# PSIO_Switchboard_PU-20_v1.net
KiCad netlist of a schematic drawn in EAGLE
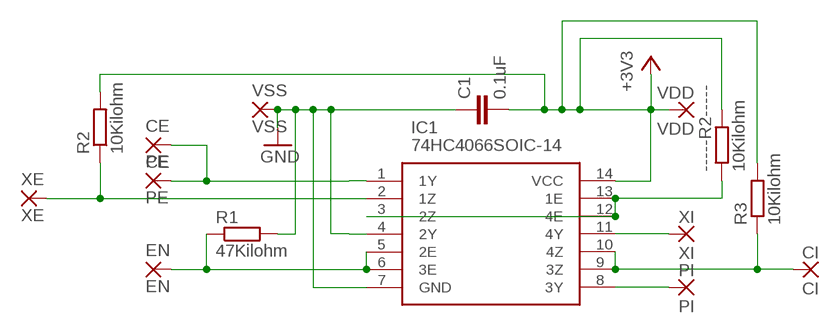
[diagram p0: schematic, sheet 1]

(export (version "E")
  (design (tool "Eeschema 10.0.6"))
  (components
    (comp (ref "-----R2-----")
      (value "10Kilohm")
      (footprint "eagle-import:R0805")
      (libsource (lib "eagle-import") (part "RESISTORSR0805"))
    )
    (comp (ref "C1")
      (value "0.1uF")
      (footprint "eagle-import:C0805")
      (libsource (lib "eagle-import") (part "CAPACITORSC0805"))
    )
    (comp (ref "CE")
      (value "CE")
      (footprint "eagle-import:CIRCLE-2X2")
      (libsource (lib "eagle-import") (part "PADSCIRCLE-2X2"))
    )
    (comp (ref "CI")
      (value "CI")
      (footprint "eagle-import:CIRCLE-2X2")
      (libsource (lib "eagle-import") (part "PADSCIRCLE-2X2"))
    )
    (comp (ref "EN")
      (value "EN")
      (footprint "eagle-import:CIRCLE-2X2")
      (libsource (lib "eagle-import") (part "PADSCIRCLE-2X2"))
    )
    (comp (ref "IC1")
      (value "74HC4066SOIC-14")
      (footprint "eagle-import:SOIC-14")
      (libsource (lib "eagle-import") (part "74HC4066SOIC-14"))
    )
    (comp (ref "PE")
      (value "PE")
      (footprint "eagle-import:CIRCLE-2X2")
      (libsource (lib "eagle-import") (part "PADSCIRCLE-2X2"))
    )
    (comp (ref "PI")
      (value "PI")
      (footprint "eagle-import:CIRCLE-2X2")
      (libsource (lib "eagle-import") (part "PADSCIRCLE-2X2"))
    )
    (comp (ref "R1")
      (value "47Kilohm")
      (footprint "eagle-import:R0805")
      (libsource (lib "eagle-import") (part "RESISTORSR0805"))
    )
    (comp (ref "R2")
      (value "10Kilohm")
      (footprint "eagle-import:R0805")
      (libsource (lib "eagle-import") (part "RESISTORSR0805"))
    )
    (comp (ref "R3")
      (value "10Kilohm")
      (footprint "eagle-import:R0805")
      (libsource (lib "eagle-import") (part "RESISTORSR0805"))
    )
    (comp (ref "VDD")
      (value "VDD")
      (footprint "eagle-import:CIRCLE-2X2")
      (libsource (lib "eagle-import") (part "PADSCIRCLE-2X2"))
    )
    (comp (ref "VSS")
      (value "VSS")
      (footprint "eagle-import:CIRCLE-2X2")
      (libsource (lib "eagle-import") (part "PADSCIRCLE-2X2"))
    )
    (comp (ref "XE")
      (value "XE")
      (footprint "eagle-import:CIRCLE-2X2")
      (libsource (lib "eagle-import") (part "PADSCIRCLE-2X2"))
    )
    (comp (ref "XI")
      (value "XI")
      (footprint "eagle-import:CIRCLE-2X2")
      (libsource (lib "eagle-import") (part "PADSCIRCLE-2X2"))
    )
  )
  (nets
    (net (code "1") (name "+3V3") (class "Default")
      (node (ref "-----R2-----") (pin "2") (pinfunction "2_2") (pintype "passive"))
      (node (ref "C1") (pin "2") (pinfunction "2_2") (pintype "passive"))
      (node (ref "IC1") (pin "14") (pinfunction "VCC_14") (pintype "bidirectional"))
      (node (ref "R2") (pin "2") (pinfunction "2_2") (pintype "passive"))
      (node (ref "R3") (pin "2") (pinfunction "2_2") (pintype "passive"))
      (node (ref "VDD") (pin "1") (pinfunction "P_1") (pintype "passive"))
    )
    (net (code "2") (name "GND") (class "Default")
      (node (ref "C1") (pin "1") (pinfunction "1_1") (pintype "passive"))
      (node (ref "IC1") (pin "4") (pinfunction "2Y_4") (pintype "bidirectional"))
      (node (ref "IC1") (pin "7") (pinfunction "GND_7") (pintype "bidirectional"))
      (node (ref "R1") (pin "2") (pinfunction "2_2") (pintype "passive"))
      (node (ref "VSS") (pin "1") (pinfunction "P_1") (pintype "passive"))
    )
    (net (code "3") (name "Net-(CE-P)") (class "Default")
      (node (ref "CE") (pin "1") (pinfunction "P_1") (pintype "passive"))
      (node (ref "IC1") (pin "1") (pinfunction "1Y_1") (pintype "bidirectional"))
      (node (ref "PE") (pin "1") (pinfunction "P_1") (pintype "passive"))
    )
    (net (code "4") (name "Net-(CI-P)") (class "Default")
      (node (ref "CI") (pin "1") (pinfunction "P_1") (pintype "passive"))
      (node (ref "IC1") (pin "10") (pinfunction "4Z_10") (pintype "bidirectional"))
      (node (ref "IC1") (pin "9") (pinfunction "3Z_9") (pintype "bidirectional"))
      (node (ref "R3") (pin "1") (pinfunction "1_1") (pintype "passive"))
    )
    (net (code "5") (name "Net-(EN-P)") (class "Default")
      (node (ref "EN") (pin "1") (pinfunction "P_1") (pintype "passive"))
      (node (ref "IC1") (pin "5") (pinfunction "2E_5") (pintype "bidirectional"))
      (node (ref "IC1") (pin "6") (pinfunction "3E_6") (pintype "bidirectional"))
      (node (ref "R1") (pin "1") (pinfunction "1_1") (pintype "passive"))
    )
    (net (code "6") (name "Net-(IC1-1E)") (class "Default")
      (node (ref "-----R2-----") (pin "1") (pinfunction "1_1") (pintype "passive"))
      (node (ref "IC1") (pin "12") (pinfunction "4E_12") (pintype "bidirectional"))
      (node (ref "IC1") (pin "13") (pinfunction "1E_13") (pintype "bidirectional"))
      (node (ref "IC1") (pin "3") (pinfunction "2Z_3") (pintype "bidirectional"))
    )
    (net (code "7") (name "Net-(IC1-1Z)") (class "Default")
      (node (ref "IC1") (pin "2") (pinfunction "1Z_2") (pintype "bidirectional"))
      (node (ref "R2") (pin "1") (pinfunction "1_1") (pintype "passive"))
      (node (ref "XE") (pin "1") (pinfunction "P_1") (pintype "passive"))
    )
    (net (code "8") (name "Net-(IC1-3Y)") (class "Default")
      (node (ref "IC1") (pin "8") (pinfunction "3Y_8") (pintype "bidirectional"))
      (node (ref "PI") (pin "1") (pinfunction "P_1") (pintype "passive"))
    )
    (net (code "9") (name "Net-(IC1-4Y)") (class "Default")
      (node (ref "IC1") (pin "11") (pinfunction "4Y_11") (pintype "bidirectional"))
      (node (ref "XI") (pin "1") (pinfunction "P_1") (pintype "passive"))
    )
  )
)
